# Sheet1.net
KiCad netlist of a schematic drawn in Altium Designer
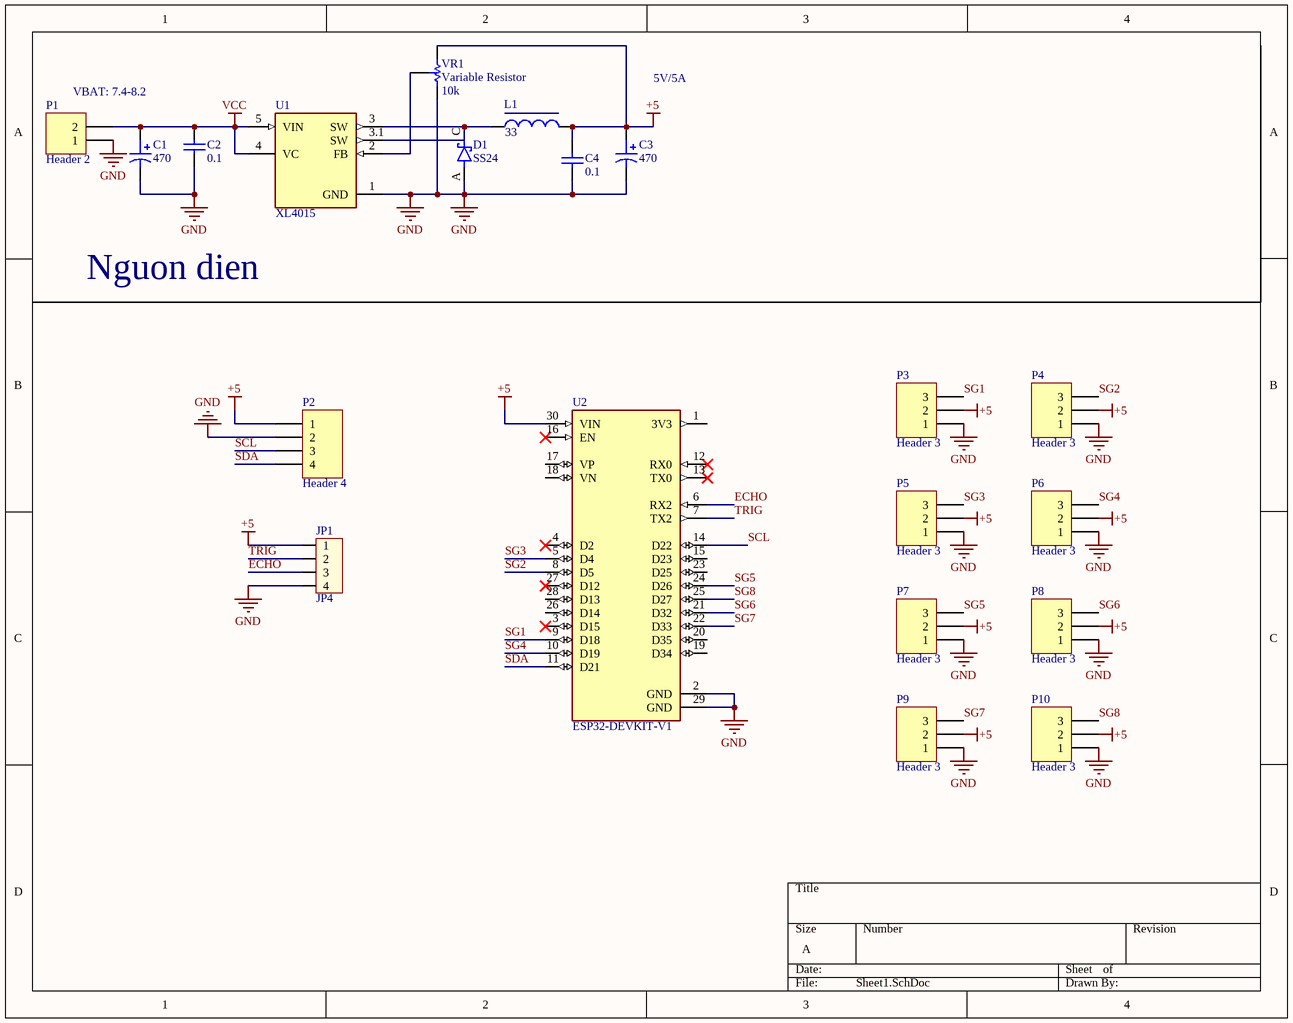
[diagram p0: Sheet1.SchDoc]

(export (version "E")
  (design (tool "Eeschema 10.0.6"))
  (components
    (comp (ref "C1")
      (value "470")
      (footprint "RADIAL E")
      (description "Polarized Capacitor")
      (fields (field (name "Comment") "Cap Pol") (field (name "PUBLISHER") "Altium Limited"))
      (libsource (lib "Kiet") (part "Cap Pol"))
    )
    (comp (ref "C2")
      (value "0.1")
      (footprint "C-NP-0805")
      (description "Non-polarized Capacitor")
      (fields (field (name "Comment") "Cap Non-pol") (field (name "PUBLISHER") "Altium Limited"))
      (libsource (lib "Kiet") (part "Cap Non-pol"))
    )
    (comp (ref "C3")
      (value "470")
      (footprint "RADIAL E")
      (description "Polarized Capacitor")
      (fields (field (name "Comment") "Cap Pol") (field (name "PUBLISHER") "Altium Limited"))
      (libsource (lib "Kiet") (part "Cap Pol"))
    )
    (comp (ref "C4")
      (value "0.1")
      (footprint "C-NP-0805")
      (description "Non-polarized Capacitor")
      (fields (field (name "Comment") "Cap Non-pol") (field (name "PUBLISHER") "Altium Limited"))
      (libsource (lib "Kiet") (part "Cap Non-pol"))
    )
    (comp (ref "D1")
      (value "SS24")
      (footprint "DIOM5336X265N")
      (description "Diode Schottky 40V 2A Surface Mount DO-214AA (SMB)")
      (fields (field (name "MF") "ON Semiconductor"))
      (libsource (lib "SS24") (part "SS24"))
    )
    (comp (ref "JP1")
      (value "JP4")
      (footprint "CON4")
      (description "Connector 4")
      (libsource (lib "Kiet") (part "Con4"))
    )
    (comp (ref "L1")
      (value "33")
      (footprint "Cuon day ferrite")
      (description "Cuon Cam L")
      (fields (field (name "PUBLISHER") "Altium Limited"))
      (libsource (lib "Kiet") (part "Inductor Ferrite"))
    )
    (comp (ref "P1")
      (value "Header 2")
      (footprint "TBlock 2")
      (description "Header, 2-Pin")
      (fields (field (name "PUBLISHER") "Altium Limited"))
      (libsource (lib "Kiet") (part "Header 2"))
    )
    (comp (ref "P2")
      (value "Header 4")
      (footprint "Header 4")
      (description "Header, 4-Pin")
      (fields (field (name "PUBLISHER") "Altium Limited"))
      (libsource (lib "Kiet") (part "Header 4"))
    )
    (comp (ref "P3")
      (value "Header 3")
      (footprint "Header 3")
      (description "Header, 3-Pin")
      (fields (field (name "PUBLISHER") "Altium Limited"))
      (libsource (lib "Kiet") (part "Header 3"))
    )
    (comp (ref "P4")
      (value "Header 3")
      (footprint "Header 3")
      (description "Header, 3-Pin")
      (fields (field (name "PUBLISHER") "Altium Limited"))
      (libsource (lib "Kiet") (part "Header 3"))
    )
    (comp (ref "P5")
      (value "Header 3")
      (footprint "Header 3")
      (description "Header, 3-Pin")
      (fields (field (name "PUBLISHER") "Altium Limited"))
      (libsource (lib "Kiet") (part "Header 3"))
    )
    (comp (ref "P6")
      (value "Header 3")
      (footprint "Header 3")
      (description "Header, 3-Pin")
      (fields (field (name "PUBLISHER") "Altium Limited"))
      (libsource (lib "Kiet") (part "Header 3"))
    )
    (comp (ref "P7")
      (value "Header 3")
      (footprint "Header 3")
      (description "Header, 3-Pin")
      (fields (field (name "PUBLISHER") "Altium Limited"))
      (libsource (lib "Kiet") (part "Header 3"))
    )
    (comp (ref "P8")
      (value "Header 3")
      (footprint "Header 3")
      (description "Header, 3-Pin")
      (fields (field (name "PUBLISHER") "Altium Limited"))
      (libsource (lib "Kiet") (part "Header 3"))
    )
    (comp (ref "P9")
      (value "Header 3")
      (footprint "Header 3")
      (description "Header, 3-Pin")
      (fields (field (name "PUBLISHER") "Altium Limited"))
      (libsource (lib "Kiet") (part "Header 3"))
    )
    (comp (ref "P10")
      (value "Header 3")
      (footprint "Header 3")
      (description "Header, 3-Pin")
      (fields (field (name "PUBLISHER") "Altium Limited"))
      (libsource (lib "Kiet") (part "Header 3"))
    )
    (comp (ref "U1")
      (value "XL4015")
      (footprint "CONV_XL4015")
      (description "5A 180KHz 36V Buck DC to DC Converter")
      (libsource (lib "XL4015") (part "XL4015"))
    )
    (comp (ref "U2")
      (value "ESP32-DEVKIT-V1")
      (footprint "MODULE_ESP32_DEVKIT_V1")
      (fields (field (name "MF") "Do it"))
      (libsource (lib "ESP32-DEVKIT-V1") (part "ESP32-DEVKIT-V1"))
    )
    (comp (ref "VR1")
      (value "Variable Resistor")
      (footprint "VRes-R")
      (fields (field (name "ALTIUM_VALUE") "10k") (field (name "PUBLISHER") "Altium Limited"))
      (libsource (lib "Kiet") (part "Variable Resistor"))
    )
  )
  (nets
    (net (code "1") (name "+5") (class "Default")
      (node (ref "C3") (pin "1") (pinfunction "1_1") (pintype "passive"))
      (node (ref "C4") (pin "1") (pinfunction "1_1") (pintype "passive"))
      (node (ref "JP1") (pin "1") (pinfunction "1_1") (pintype "passive"))
      (node (ref "L1") (pin "2") (pinfunction "2_2") (pintype "passive"))
      (node (ref "P10") (pin "2") (pinfunction "2_2") (pintype "passive"))
      (node (ref "P2") (pin "1") (pinfunction "1_1") (pintype "passive"))
      (node (ref "P3") (pin "2") (pinfunction "2_2") (pintype "passive"))
      (node (ref "P4") (pin "2") (pinfunction "2_2") (pintype "passive"))
      (node (ref "P5") (pin "2") (pinfunction "2_2") (pintype "passive"))
      (node (ref "P6") (pin "2") (pinfunction "2_2") (pintype "passive"))
      (node (ref "P7") (pin "2") (pinfunction "2_2") (pintype "passive"))
      (node (ref "P8") (pin "2") (pinfunction "2_2") (pintype "passive"))
      (node (ref "P9") (pin "2") (pinfunction "2_2") (pintype "passive"))
      (node (ref "U2") (pin "30") (pinfunction "VIN_30") (pintype "input"))
      (node (ref "VR1") (pin "1") (pinfunction "1_1") (pintype "passive"))
    )
    (net (code "2") (name "/ECHO") (class "Default")
      (node (ref "JP1") (pin "3") (pinfunction "3_3") (pintype "passive"))
      (node (ref "U2") (pin "6") (pinfunction "RX2_6") (pintype "input"))
    )
    (net (code "3") (name "/SCL") (class "Default")
      (node (ref "P2") (pin "3") (pinfunction "3_3") (pintype "passive"))
      (node (ref "U2") (pin "14") (pinfunction "D22_14") (pintype "bidirectional"))
    )
    (net (code "4") (name "/SDA") (class "Default")
      (node (ref "P2") (pin "4") (pinfunction "4_4") (pintype "passive"))
      (node (ref "U2") (pin "11") (pinfunction "D21_11") (pintype "bidirectional"))
    )
    (net (code "5") (name "/SG1") (class "Default")
      (node (ref "P3") (pin "3") (pinfunction "3_3") (pintype "passive"))
      (node (ref "U2") (pin "9") (pinfunction "D18_9") (pintype "bidirectional"))
    )
    (net (code "6") (name "/SG2") (class "Default")
      (node (ref "P4") (pin "3") (pinfunction "3_3") (pintype "passive"))
      (node (ref "U2") (pin "8") (pinfunction "D5_8") (pintype "bidirectional"))
    )
    (net (code "7") (name "/SG3") (class "Default")
      (node (ref "P5") (pin "3") (pinfunction "3_3") (pintype "passive"))
      (node (ref "U2") (pin "5") (pinfunction "D4_5") (pintype "bidirectional"))
    )
    (net (code "8") (name "/SG4") (class "Default")
      (node (ref "P6") (pin "3") (pinfunction "3_3") (pintype "passive"))
      (node (ref "U2") (pin "10") (pinfunction "D19_10") (pintype "bidirectional"))
    )
    (net (code "9") (name "/SG5") (class "Default")
      (node (ref "P7") (pin "3") (pinfunction "3_3") (pintype "passive"))
      (node (ref "U2") (pin "24") (pinfunction "D26_24") (pintype "bidirectional"))
    )
    (net (code "10") (name "/SG6") (class "Default")
      (node (ref "P8") (pin "3") (pinfunction "3_3") (pintype "passive"))
      (node (ref "U2") (pin "21") (pinfunction "D32_21") (pintype "bidirectional"))
    )
    (net (code "11") (name "/SG7") (class "Default")
      (node (ref "P9") (pin "3") (pinfunction "3_3") (pintype "passive"))
      (node (ref "U2") (pin "22") (pinfunction "D33_22") (pintype "bidirectional"))
    )
    (net (code "12") (name "/SG8") (class "Default")
      (node (ref "P10") (pin "3") (pinfunction "3_3") (pintype "passive"))
      (node (ref "U2") (pin "25") (pinfunction "D27_25") (pintype "bidirectional"))
    )
    (net (code "13") (name "/TRIG") (class "Default")
      (node (ref "JP1") (pin "2") (pinfunction "2_2") (pintype "passive"))
      (node (ref "U2") (pin "7") (pinfunction "TX2_7") (pintype "output"))
    )
    (net (code "14") (name "GND") (class "Default")
      (node (ref "C1") (pin "2") (pinfunction "2_2") (pintype "passive"))
      (node (ref "C2") (pin "1") (pinfunction "1_1") (pintype "passive"))
      (node (ref "C3") (pin "2") (pinfunction "2_2") (pintype "passive"))
      (node (ref "C4") (pin "2") (pinfunction "2_2") (pintype "passive"))
      (node (ref "D1") (pin "A") (pinfunction "A_A") (pintype "passive"))
      (node (ref "JP1") (pin "4") (pinfunction "4_4") (pintype "passive"))
      (node (ref "P1") (pin "1") (pinfunction "1_1") (pintype "passive"))
      (node (ref "P10") (pin "1") (pinfunction "1_1") (pintype "passive"))
      (node (ref "P2") (pin "2") (pinfunction "2_2") (pintype "passive"))
      (node (ref "P3") (pin "1") (pinfunction "1_1") (pintype "passive"))
      (node (ref "P4") (pin "1") (pinfunction "1_1") (pintype "passive"))
      (node (ref "P5") (pin "1") (pinfunction "1_1") (pintype "passive"))
      (node (ref "P6") (pin "1") (pinfunction "1_1") (pintype "passive"))
      (node (ref "P7") (pin "1") (pinfunction "1_1") (pintype "passive"))
      (node (ref "P8") (pin "1") (pinfunction "1_1") (pintype "passive"))
      (node (ref "P9") (pin "1") (pinfunction "1_1") (pintype "passive"))
      (node (ref "U1") (pin "1") (pinfunction "GND_1") (pintype "power_in"))
      (node (ref "U2") (pin "2") (pinfunction "GND_2") (pintype "power_in"))
      (node (ref "U2") (pin "29") (pinfunction "GND_29") (pintype "power_in"))
      (node (ref "VR1") (pin "3") (pinfunction "3_3") (pintype "passive"))
    )
    (net (code "15") (name "Net-(D1-K)") (class "Default")
      (node (ref "D1") (pin "C") (pinfunction "K_C") (pintype "passive"))
      (node (ref "L1") (pin "1") (pinfunction "1_1") (pintype "passive"))
      (node (ref "U1") (pin "3") (pinfunction "SW_3") (pintype "output"))
      (node (ref "U1") (pin "3.1") (pinfunction "SW_3.1") (pintype "output"))
    )
    (net (code "16") (name "Net-(U1-FB)") (class "Default")
      (node (ref "U1") (pin "2") (pinfunction "FB_2") (pintype "input"))
      (node (ref "VR1") (pin "2") (pinfunction "2_2") (pintype "passive"))
    )
    (net (code "17") (name "VCC") (class "Default")
      (node (ref "C1") (pin "1") (pinfunction "1_1") (pintype "passive"))
      (node (ref "C2") (pin "2") (pinfunction "2_2") (pintype "passive"))
      (node (ref "P1") (pin "2") (pinfunction "2_2") (pintype "passive"))
      (node (ref "U1") (pin "4") (pinfunction "VC_4") (pintype "passive"))
      (node (ref "U1") (pin "5") (pinfunction "VIN_5") (pintype "input"))
    )
    (net (code "18") (name "unconnected-(U2-3V3-Pad1)") (class "Default")
      (node (ref "U2") (pin "1") (pinfunction "3V3_1") (pintype "output"))
    )
    (net (code "19") (name "unconnected-(U2-D2-Pad4)") (class "Default")
      (node (ref "U2") (pin "4") (pinfunction "D2_4") (pintype "bidirectional+no_connect"))
    )
    (net (code "20") (name "unconnected-(U2-D12-Pad27)") (class "Default")
      (node (ref "U2") (pin "27") (pinfunction "D12_27") (pintype "bidirectional+no_connect"))
    )
    (net (code "21") (name "unconnected-(U2-D13-Pad28)") (class "Default")
      (node (ref "U2") (pin "28") (pinfunction "D13_28") (pintype "bidirectional"))
    )
    (net (code "22") (name "unconnected-(U2-D14-Pad26)") (class "Default")
      (node (ref "U2") (pin "26") (pinfunction "D14_26") (pintype "bidirectional"))
    )
    (net (code "23") (name "unconnected-(U2-D15-Pad3)") (class "Default")
      (node (ref "U2") (pin "3") (pinfunction "D15_3") (pintype "bidirectional+no_connect"))
    )
    (net (code "24") (name "unconnected-(U2-D23-Pad15)") (class "Default")
      (node (ref "U2") (pin "15") (pinfunction "D23_15") (pintype "bidirectional"))
    )
    (net (code "25") (name "unconnected-(U2-D25-Pad23)") (class "Default")
      (node (ref "U2") (pin "23") (pinfunction "D25_23") (pintype "bidirectional"))
    )
    (net (code "26") (name "unconnected-(U2-D34-Pad19)") (class "Default")
      (node (ref "U2") (pin "19") (pinfunction "D34_19") (pintype "bidirectional"))
    )
    (net (code "27") (name "unconnected-(U2-D35-Pad20)") (class "Default")
      (node (ref "U2") (pin "20") (pinfunction "D35_20") (pintype "bidirectional"))
    )
    (net (code "28") (name "unconnected-(U2-EN-Pad16)") (class "Default")
      (node (ref "U2") (pin "16") (pinfunction "EN_16") (pintype "input+no_connect"))
    )
    (net (code "29") (name "unconnected-(U2-RX0-Pad12)") (class "Default")
      (node (ref "U2") (pin "12") (pinfunction "RX0_12") (pintype "input+no_connect"))
    )
    (net (code "30") (name "unconnected-(U2-TX0-Pad13)") (class "Default")
      (node (ref "U2") (pin "13") (pinfunction "TX0_13") (pintype "output+no_connect"))
    )
    (net (code "31") (name "unconnected-(U2-VN-Pad18)") (class "Default")
      (node (ref "U2") (pin "18") (pinfunction "VN_18") (pintype "bidirectional"))
    )
    (net (code "32") (name "unconnected-(U2-VP-Pad17)") (class "Default")
      (node (ref "U2") (pin "17") (pinfunction "VP_17") (pintype "bidirectional"))
    )
  )
)
